# exhaust_gas_temp_oxy.net
KiCad netlist of a schematic drawn in Altium Designer
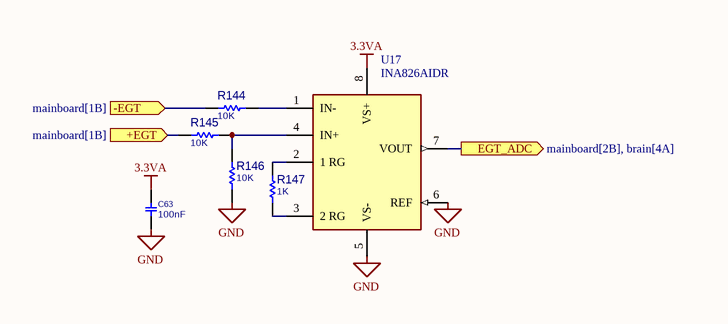
[diagram p0: exhaust_gas_temp_oxy.SchDoc]

(export (version "E")
  (design (tool "Eeschema 10.0.6"))
  (components
    (comp (ref "C63")
      (value "100nF")
      (footprint "C0805")
      (description "CAP, MLCC")
      (fields (field (name "MANF_P#") "MANF_PART#"))
      (libsource (lib "passive_smd") (part "CAP_SMD_MLCC_0805"))
    )
    (comp (ref "R144")
      (value "10K")
      (footprint "R0805")
      (description "RESISTOR, SMD")
      (libsource (lib "passive_smd") (part "RES_SMD_0805"))
    )
    (comp (ref "R145")
      (value "10K")
      (footprint "R0805")
      (description "RESISTOR, SMD")
      (libsource (lib "passive_smd") (part "RES_SMD_0805"))
    )
    (comp (ref "R146")
      (value "10K")
      (footprint "R0805")
      (description "RESISTOR, SMD")
      (libsource (lib "passive_smd") (part "RES_SMD_0805"))
    )
    (comp (ref "R147")
      (value "1K")
      (footprint "R0805")
      (description "RESISTOR, SMD")
      (libsource (lib "passive_smd") (part "RES_SMD_0805"))
    )
    (comp (ref "U17")
      (value "INA826AIDR")
      (footprint "SOIC-8")
      (description "IC INST AMP 1 CIRCUIT 8SOIC")
      (libsource (lib "alib") (part "INA826"))
    )
  )
  (nets
    (net (code "1") (name "/+EGT") (class "Default")
      (node (ref "R145") (pin "1") (pinfunction "1_1") (pintype "passive"))
    )
    (net (code "2") (name "/-EGT") (class "Default")
      (node (ref "R144") (pin "2") (pinfunction "2_2") (pintype "passive"))
    )
    (net (code "3") (name "/EGT_ADC") (class "Default")
      (node (ref "U17") (pin "7") (pinfunction "VOUT_7") (pintype "output"))
    )
    (net (code "4") (name "3.3VA") (class "Default")
      (node (ref "C63") (pin "2") (pinfunction "2_2") (pintype "passive"))
      (node (ref "U17") (pin "8") (pinfunction "VS+_8") (pintype "power_in"))
    )
    (net (code "5") (name "GND") (class "Default")
      (node (ref "C63") (pin "1") (pinfunction "1_1") (pintype "passive"))
      (node (ref "R146") (pin "1") (pinfunction "1_1") (pintype "passive"))
      (node (ref "U17") (pin "5") (pinfunction "VS-_5") (pintype "power_in"))
      (node (ref "U17") (pin "6") (pinfunction "REF_6") (pintype "input"))
    )
    (net (code "6") (name "Net-(U17-1_RG)") (class "Default")
      (node (ref "R147") (pin "2") (pinfunction "2_2") (pintype "passive"))
      (node (ref "U17") (pin "2") (pinfunction "1_RG_2") (pintype "passive"))
    )
    (net (code "7") (name "Net-(U17-2_RG)") (class "Default")
      (node (ref "R147") (pin "1") (pinfunction "1_1") (pintype "passive"))
      (node (ref "U17") (pin "3") (pinfunction "2_RG_3") (pintype "passive"))
    )
    (net (code "8") (name "Net-(U17-IN+)") (class "Default")
      (node (ref "R145") (pin "2") (pinfunction "2_2") (pintype "passive"))
      (node (ref "R146") (pin "2") (pinfunction "2_2") (pintype "passive"))
      (node (ref "U17") (pin "4") (pinfunction "IN+_4") (pintype "passive"))
    )
    (net (code "9") (name "Net-(U17-IN-)") (class "Default")
      (node (ref "R144") (pin "1") (pinfunction "1_1") (pintype "passive"))
      (node (ref "U17") (pin "1") (pinfunction "IN-_1") (pintype "power_in"))
    )
  )
)
